# MagicRadio2.net
KiCad netlist of a schematic drawn in EAGLE
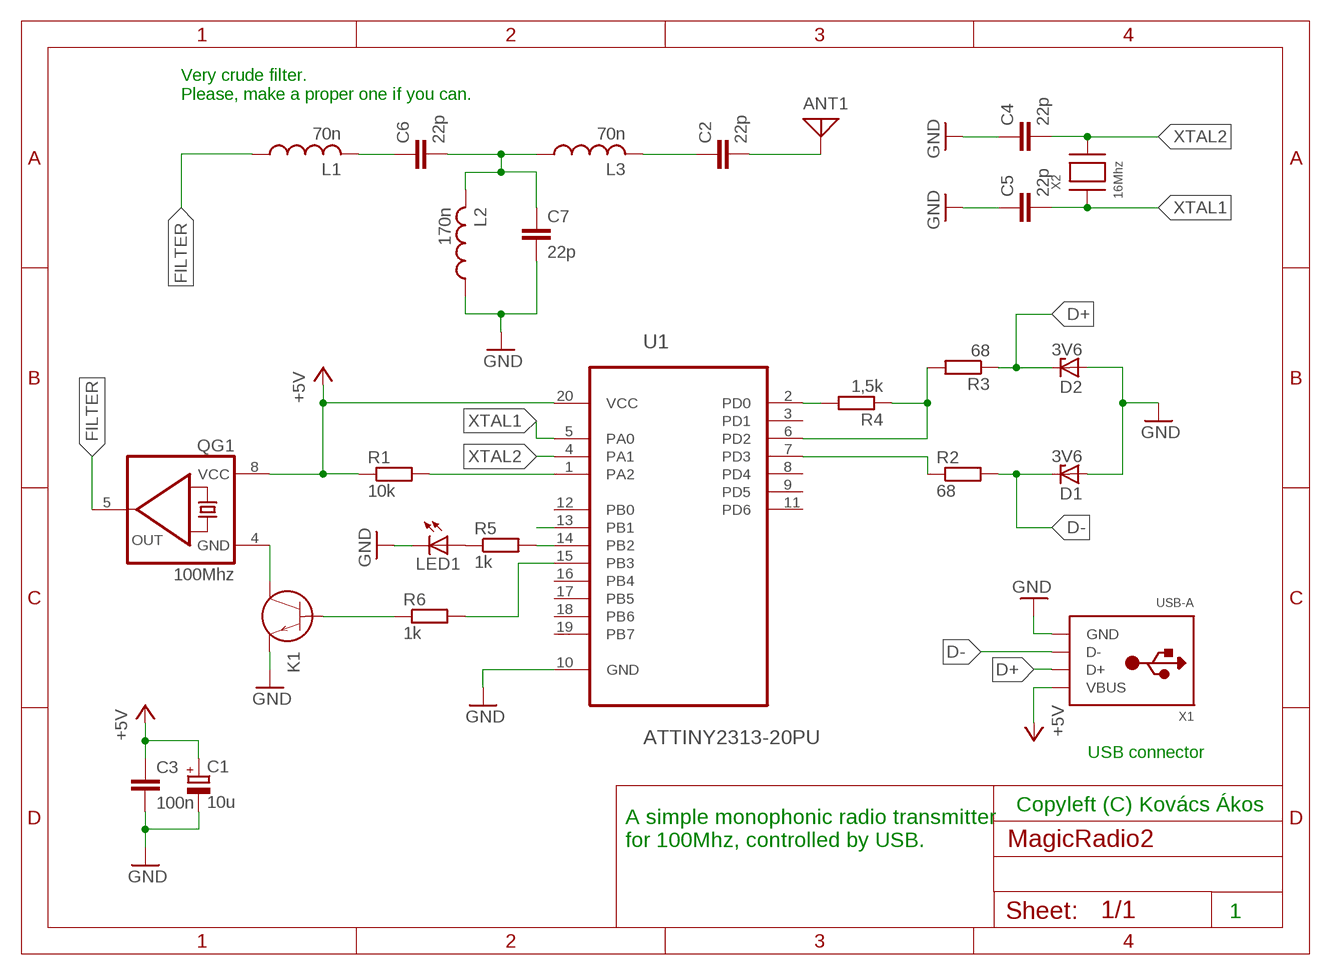
[diagram p0: schematic, sheet 1]

(export (version "E")
  (design (tool "Eeschema 10.0.6"))
  (components
    (comp (ref "ANT1")
      (value "ANTENNA")
      (footprint "eagle-import:PAD-01")
      (libsource (lib "eagle-import") (part "ANTENNA"))
    )
    (comp (ref "C1")
      (value "10u")
      (footprint "eagle-import:E2,5-6")
      (libsource (lib "eagle-import") (part "CPOL-EUE2.5-6"))
    )
    (comp (ref "C2")
      (value "22p")
      (footprint "eagle-import:C025-024X044")
      (libsource (lib "eagle-import") (part "C-EU025-024X044"))
    )
    (comp (ref "C3")
      (value "100n")
      (footprint "eagle-import:C025-024X044")
      (libsource (lib "eagle-import") (part "C-EU025-024X044"))
    )
    (comp (ref "C4")
      (value "22p")
      (footprint "eagle-import:C025-024X044")
      (libsource (lib "eagle-import") (part "C-EU025-024X044"))
    )
    (comp (ref "C5")
      (value "22p")
      (footprint "eagle-import:C025-024X044")
      (libsource (lib "eagle-import") (part "C-EU025-024X044"))
    )
    (comp (ref "C6")
      (value "22p")
      (footprint "eagle-import:C025-024X044")
      (libsource (lib "eagle-import") (part "C-EU025-024X044"))
    )
    (comp (ref "C7")
      (value "22p")
      (footprint "eagle-import:C025-024X044")
      (libsource (lib "eagle-import") (part "C-EU025-024X044"))
    )
    (comp (ref "D1")
      (value "3V6")
      (footprint "eagle-import:DO34Z7")
      (libsource (lib "eagle-import") (part "ZENER-DIODEDO34-7"))
    )
    (comp (ref "D2")
      (value "3V6")
      (footprint "eagle-import:DO34Z7")
      (libsource (lib "eagle-import") (part "ZENER-DIODEDO34-7"))
    )
    (comp (ref "K1")
      (value "NPN-TRANSISTOR")
      (footprint "eagle-import:NPN-TRANSISTOR")
      (libsource (lib "eagle-import") (part "NPN-TRANSISTOR"))
    )
    (comp (ref "L1")
      (value "70n")
      (footprint "eagle-import:TFI0307")
      (libsource (lib "eagle-import") (part "L-USTFI0307"))
    )
    (comp (ref "L2")
      (value "170n")
      (footprint "eagle-import:TFI0307")
      (libsource (lib "eagle-import") (part "L-USTFI0307"))
    )
    (comp (ref "L3")
      (value "70n")
      (footprint "eagle-import:TFI0307")
      (libsource (lib "eagle-import") (part "L-USTFI0307"))
    )
    (comp (ref "LED1")
      (value "LED")
      (footprint "eagle-import:SMARTLED-TTW")
      (libsource (lib "eagle-import") (part "LED"))
    )
    (comp (ref "QG1")
      (value "100Mhz")
      (footprint "eagle-import:DIL08S")
      (libsource (lib "eagle-import") (part "QG5460"))
    )
    (comp (ref "R1")
      (value "10k")
      (footprint "eagle-import:0204_5")
      (libsource (lib "eagle-import") (part "R-EU_0204/5"))
    )
    (comp (ref "R2")
      (value "68")
      (footprint "eagle-import:0204_5")
      (libsource (lib "eagle-import") (part "R-EU_0204/5"))
    )
    (comp (ref "R3")
      (value "68")
      (footprint "eagle-import:0204_5")
      (libsource (lib "eagle-import") (part "R-EU_0204/5"))
    )
    (comp (ref "R4")
      (value "1,5k")
      (footprint "eagle-import:0204_5")
      (libsource (lib "eagle-import") (part "R-EU_0204/5"))
    )
    (comp (ref "R5")
      (value "1k")
      (footprint "eagle-import:0204_5")
      (libsource (lib "eagle-import") (part "R-EU_0204/5"))
    )
    (comp (ref "R6")
      (value "1k")
      (footprint "eagle-import:0204_5")
      (libsource (lib "eagle-import") (part "R-EU_0204/5"))
    )
    (comp (ref "U1")
      (value "ATTINY2313-20PU")
      (footprint "eagle-import:DIP254P762X533-20")
      (libsource (lib "eagle-import") (part "ATTINY2313-20PU"))
    )
    (comp (ref "X1")
      (value "USB-A")
      (footprint "eagle-import:MOLEX_480371000")
      (libsource (lib "eagle-import") (part "USB-A"))
    )
    (comp (ref "X2")
      (value "16Mhz")
      (footprint "eagle-import:XTAL3215")
      (libsource (lib "eagle-import") (part "XTAL-3.2X1.5"))
    )
  )
  (nets
    (net (code "1") (name "+5V") (class "Default")
      (node (ref "C1") (pin "+") (pinfunction "+_+") (pintype "passive"))
      (node (ref "C3") (pin "1") (pinfunction "1_1") (pintype "passive"))
      (node (ref "QG1") (pin "8") (pinfunction "VCC_8") (pintype "power_in"))
      (node (ref "R1") (pin "1") (pinfunction "1_1") (pintype "passive"))
      (node (ref "U1") (pin "20") (pinfunction "VCC_20") (pintype "power_in"))
      (node (ref "X1") (pin "1") (pinfunction "VBUS_1") (pintype "power_in"))
    )
    (net (code "2") (name "D+") (class "Default")
      (node (ref "D2") (pin "C") (pinfunction "C_C") (pintype "passive"))
      (node (ref "R3") (pin "1") (pinfunction "1_1") (pintype "passive"))
      (node (ref "X1") (pin "3") (pinfunction "D+_3") (pintype "bidirectional"))
    )
    (net (code "3") (name "D-") (class "Default")
      (node (ref "D1") (pin "C") (pinfunction "C_C") (pintype "passive"))
      (node (ref "R2") (pin "2") (pinfunction "2_2") (pintype "passive"))
      (node (ref "X1") (pin "2") (pinfunction "D-_2") (pintype "bidirectional"))
    )
    (net (code "4") (name "FILTER") (class "Default")
      (node (ref "L1") (pin "1") (pinfunction "1_1") (pintype "passive"))
      (node (ref "QG1") (pin "5") (pinfunction "OUT_5") (pintype "output"))
    )
    (net (code "5") (name "GND") (class "Default")
      (node (ref "C1") (pin "-") (pinfunction "-_-") (pintype "passive"))
      (node (ref "C3") (pin "2") (pinfunction "2_2") (pintype "passive"))
      (node (ref "C4") (pin "1") (pinfunction "1_1") (pintype "passive"))
      (node (ref "C5") (pin "1") (pinfunction "1_1") (pintype "passive"))
      (node (ref "C7") (pin "2") (pinfunction "2_2") (pintype "passive"))
      (node (ref "D1") (pin "A") (pinfunction "A_A") (pintype "passive"))
      (node (ref "D2") (pin "A") (pinfunction "A_A") (pintype "passive"))
      (node (ref "K1") (pin "E") (pinfunction "E_E") (pintype "input"))
      (node (ref "L2") (pin "1") (pinfunction "1_1") (pintype "passive"))
      (node (ref "LED1") (pin "C@1") (pinfunction "C_C@1") (pintype "passive"))
      (node (ref "U1") (pin "10") (pinfunction "GND_10") (pintype "passive"))
      (node (ref "X1") (pin "4") (pinfunction "GND_4") (pintype "power_in"))
    )
    (net (code "6") (name "Net-(ANT1-Pad1)") (class "Default")
      (node (ref "ANT1") (pin "1") (pinfunction "1_1") (pintype "output"))
      (node (ref "C2") (pin "2") (pinfunction "2_2") (pintype "passive"))
    )
    (net (code "7") (name "Net-(C2-Pad1)") (class "Default")
      (node (ref "C2") (pin "1") (pinfunction "1_1") (pintype "passive"))
      (node (ref "L3") (pin "2") (pinfunction "2_2") (pintype "passive"))
    )
    (net (code "8") (name "Net-(C6-Pad1)") (class "Default")
      (node (ref "C6") (pin "1") (pinfunction "1_1") (pintype "passive"))
      (node (ref "L1") (pin "2") (pinfunction "2_2") (pintype "passive"))
    )
    (net (code "9") (name "Net-(C6-Pad2)") (class "Default")
      (node (ref "C6") (pin "2") (pinfunction "2_2") (pintype "passive"))
      (node (ref "C7") (pin "1") (pinfunction "1_1") (pintype "passive"))
      (node (ref "L2") (pin "2") (pinfunction "2_2") (pintype "passive"))
      (node (ref "L3") (pin "1") (pinfunction "1_1") (pintype "passive"))
    )
    (net (code "10") (name "Net-(K1-PadB)") (class "Default")
      (node (ref "K1") (pin "B") (pinfunction "B_B") (pintype "input"))
      (node (ref "R6") (pin "1") (pinfunction "1_1") (pintype "passive"))
    )
    (net (code "11") (name "Net-(LED1-A)") (class "Default")
      (node (ref "LED1") (pin "A@1") (pinfunction "A_A@1") (pintype "passive"))
      (node (ref "R5") (pin "1") (pinfunction "1_1") (pintype "passive"))
    )
    (net (code "12") (name "Net-(QG1-GND)") (class "Default")
      (node (ref "K1") (pin "C") (pinfunction "C_C") (pintype "input"))
      (node (ref "QG1") (pin "4") (pinfunction "GND_4") (pintype "power_in"))
    )
    (net (code "13") (name "Net-(U1-PA2)") (class "Default")
      (node (ref "R1") (pin "2") (pinfunction "2_2") (pintype "passive"))
      (node (ref "U1") (pin "1") (pinfunction "PA2_1") (pintype "bidirectional"))
    )
    (net (code "14") (name "Net-(U1-PB2)") (class "Default")
      (node (ref "R5") (pin "2") (pinfunction "2_2") (pintype "passive"))
      (node (ref "U1") (pin "14") (pinfunction "PB2_14") (pintype "bidirectional"))
    )
    (net (code "15") (name "Net-(U1-PB3)") (class "Default")
      (node (ref "R6") (pin "2") (pinfunction "2_2") (pintype "passive"))
      (node (ref "U1") (pin "15") (pinfunction "PB3_15") (pintype "bidirectional"))
    )
    (net (code "16") (name "Net-(U1-PD0)") (class "Default")
      (node (ref "R4") (pin "2") (pinfunction "2_2") (pintype "passive"))
      (node (ref "U1") (pin "2") (pinfunction "PD0_2") (pintype "bidirectional"))
    )
    (net (code "17") (name "Net-(U1-PD2)") (class "Default")
      (node (ref "R3") (pin "2") (pinfunction "2_2") (pintype "passive"))
      (node (ref "R4") (pin "1") (pinfunction "1_1") (pintype "passive"))
      (node (ref "U1") (pin "6") (pinfunction "PD2_6") (pintype "bidirectional"))
    )
    (net (code "18") (name "Net-(U1-PD3)") (class "Default")
      (node (ref "R2") (pin "1") (pinfunction "1_1") (pintype "passive"))
      (node (ref "U1") (pin "7") (pinfunction "PD3_7") (pintype "bidirectional"))
    )
    (net (code "19") (name "XTAL1") (class "Default")
      (node (ref "C5") (pin "2") (pinfunction "2_2") (pintype "passive"))
      (node (ref "U1") (pin "5") (pinfunction "PA0_5") (pintype "bidirectional"))
      (node (ref "X2") (pin "P$1") (pinfunction "P$1_P$1") (pintype "bidirectional"))
    )
    (net (code "20") (name "XTAL2") (class "Default")
      (node (ref "C4") (pin "2") (pinfunction "2_2") (pintype "passive"))
      (node (ref "U1") (pin "4") (pinfunction "PA1_4") (pintype "bidirectional"))
      (node (ref "X2") (pin "P$2") (pinfunction "P$2_P$2") (pintype "bidirectional"))
    )
    (net (code "21") (name "unconnected-(U1-PB0-Pad12)") (class "Default")
      (node (ref "U1") (pin "12") (pinfunction "PB0_12") (pintype "bidirectional"))
    )
    (net (code "22") (name "unconnected-(U1-PB1-Pad13)") (class "Default")
      (node (ref "U1") (pin "13") (pinfunction "PB1_13") (pintype "bidirectional"))
    )
    (net (code "23") (name "unconnected-(U1-PB4-Pad16)") (class "Default")
      (node (ref "U1") (pin "16") (pinfunction "PB4_16") (pintype "bidirectional"))
    )
    (net (code "24") (name "unconnected-(U1-PB5-Pad17)") (class "Default")
      (node (ref "U1") (pin "17") (pinfunction "PB5_17") (pintype "bidirectional"))
    )
    (net (code "25") (name "unconnected-(U1-PB6-Pad18)") (class "Default")
      (node (ref "U1") (pin "18") (pinfunction "PB6_18") (pintype "bidirectional"))
    )
    (net (code "26") (name "unconnected-(U1-PB7-Pad19)") (class "Default")
      (node (ref "U1") (pin "19") (pinfunction "PB7_19") (pintype "bidirectional"))
    )
    (net (code "27") (name "unconnected-(U1-PD1-Pad3)") (class "Default")
      (node (ref "U1") (pin "3") (pinfunction "PD1_3") (pintype "bidirectional"))
    )
    (net (code "28") (name "unconnected-(U1-PD4-Pad8)") (class "Default")
      (node (ref "U1") (pin "8") (pinfunction "PD4_8") (pintype "bidirectional"))
    )
    (net (code "29") (name "unconnected-(U1-PD5-Pad9)") (class "Default")
      (node (ref "U1") (pin "9") (pinfunction "PD5_9") (pintype "bidirectional"))
    )
    (net (code "30") (name "unconnected-(U1-PD6-Pad11)") (class "Default")
      (node (ref "U1") (pin "11") (pinfunction "PD6_11") (pintype "bidirectional"))
    )
  )
)
